# RT9187.net
KiCad netlist of a schematic drawn in Altium Designer
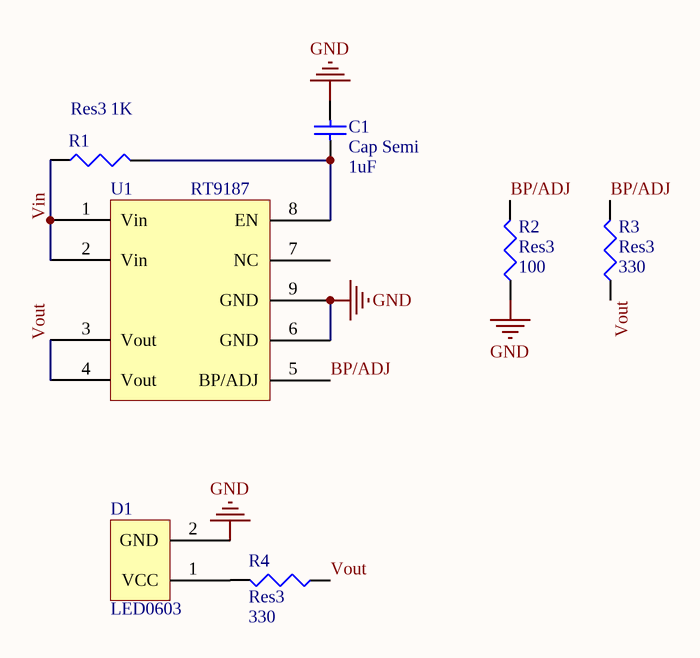
[diagram p0: RT9187.SchDoc]

(export (version "E")
  (design (tool "Eeschema 10.0.6"))
  (components
    (comp (ref "C1")
      (value "Cap Semi")
      (footprint "1608[0603]")
      (description "Capacitor (Semiconductor SIM Model)")
      (fields (field (name "ALTIUM_VALUE") "1uF") (field (name "PUBLISHER") "Altium Limited"))
      (libsource (lib "Miscellaneous Devices") (part "Cap Semi"))
    )
    (comp (ref "D1") (value "LED0603") (footprint "LED0603") (libsource (lib "RT9187") (part "LED0603")))
    (comp (ref "R1")
      (value "Res3")
      (footprint "J1-0603")
      (description "Resistor")
      (fields (field (name "ALTIUM_VALUE") "1K") (field (name "PUBLISHER") "Altium Limited"))
      (libsource (lib "Miscellaneous Devices") (part "Res3"))
    )
    (comp (ref "R2")
      (value "Res3")
      (footprint "J1-0603")
      (description "Resistor")
      (fields (field (name "ALTIUM_VALUE") "100") (field (name "PUBLISHER") "Altium Limited"))
      (libsource (lib "Miscellaneous Devices") (part "Res3"))
    )
    (comp (ref "R3")
      (value "Res3")
      (footprint "J1-0603")
      (description "Resistor")
      (fields (field (name "ALTIUM_VALUE") "330") (field (name "PUBLISHER") "Altium Limited"))
      (libsource (lib "Miscellaneous Devices") (part "Res3"))
    )
    (comp (ref "R4")
      (value "Res3")
      (footprint "J1-0603")
      (description "Resistor")
      (fields (field (name "ALTIUM_VALUE") "330") (field (name "PUBLISHER") "Altium Limited"))
      (libsource (lib "Miscellaneous Devices") (part "Res3"))
    )
    (comp (ref "U1") (value "RT9187") (footprint "RT9187") (libsource (lib "RT9187") (part "RT9187")))
  )
  (nets
    (net (code "1") (name "/BP{slash}ADJ") (class "Default")
      (node (ref "R2") (pin "2") (pinfunction "2_2") (pintype "passive"))
      (node (ref "R3") (pin "2") (pinfunction "2_2") (pintype "passive"))
      (node (ref "U1") (pin "5") (pinfunction "BP/ADJ_5") (pintype "passive"))
    )
    (net (code "2") (name "/Vin") (class "Default")
      (node (ref "R1") (pin "1") (pinfunction "1_1") (pintype "passive"))
      (node (ref "U1") (pin "1") (pinfunction "Vin_1") (pintype "passive"))
      (node (ref "U1") (pin "2") (pinfunction "Vin_2") (pintype "passive"))
    )
    (net (code "3") (name "/Vout") (class "Default")
      (node (ref "R3") (pin "1") (pinfunction "1_1") (pintype "passive"))
      (node (ref "R4") (pin "1") (pinfunction "1_1") (pintype "passive"))
      (node (ref "U1") (pin "3") (pinfunction "Vout_3") (pintype "passive"))
      (node (ref "U1") (pin "4") (pinfunction "Vout_4") (pintype "passive"))
    )
    (net (code "4") (name "GND") (class "Default")
      (node (ref "C1") (pin "1") (pinfunction "1_1") (pintype "passive"))
      (node (ref "D1") (pin "2") (pinfunction "GND_2") (pintype "passive"))
      (node (ref "R2") (pin "1") (pinfunction "1_1") (pintype "passive"))
      (node (ref "U1") (pin "6") (pinfunction "GND_6") (pintype "passive"))
      (node (ref "U1") (pin "9") (pinfunction "GND_9") (pintype "passive"))
    )
    (net (code "5") (name "Net-(D1-VCC)") (class "Default")
      (node (ref "D1") (pin "1") (pinfunction "VCC_1") (pintype "passive"))
      (node (ref "R4") (pin "2") (pinfunction "2_2") (pintype "passive"))
    )
    (net (code "6") (name "Net-(U1-EN)") (class "Default")
      (node (ref "C1") (pin "2") (pinfunction "2_2") (pintype "passive"))
      (node (ref "R1") (pin "2") (pinfunction "2_2") (pintype "passive"))
      (node (ref "U1") (pin "8") (pinfunction "EN_8") (pintype "passive"))
    )
    (net (code "7") (name "unconnected-(U1-NC-Pad7)") (class "Default")
      (node (ref "U1") (pin "7") (pinfunction "NC_7") (pintype "passive"))
    )
  )
)
